# x-IMU3-SA-A8.net
KiCad netlist of a schematic drawn in Altium Designer
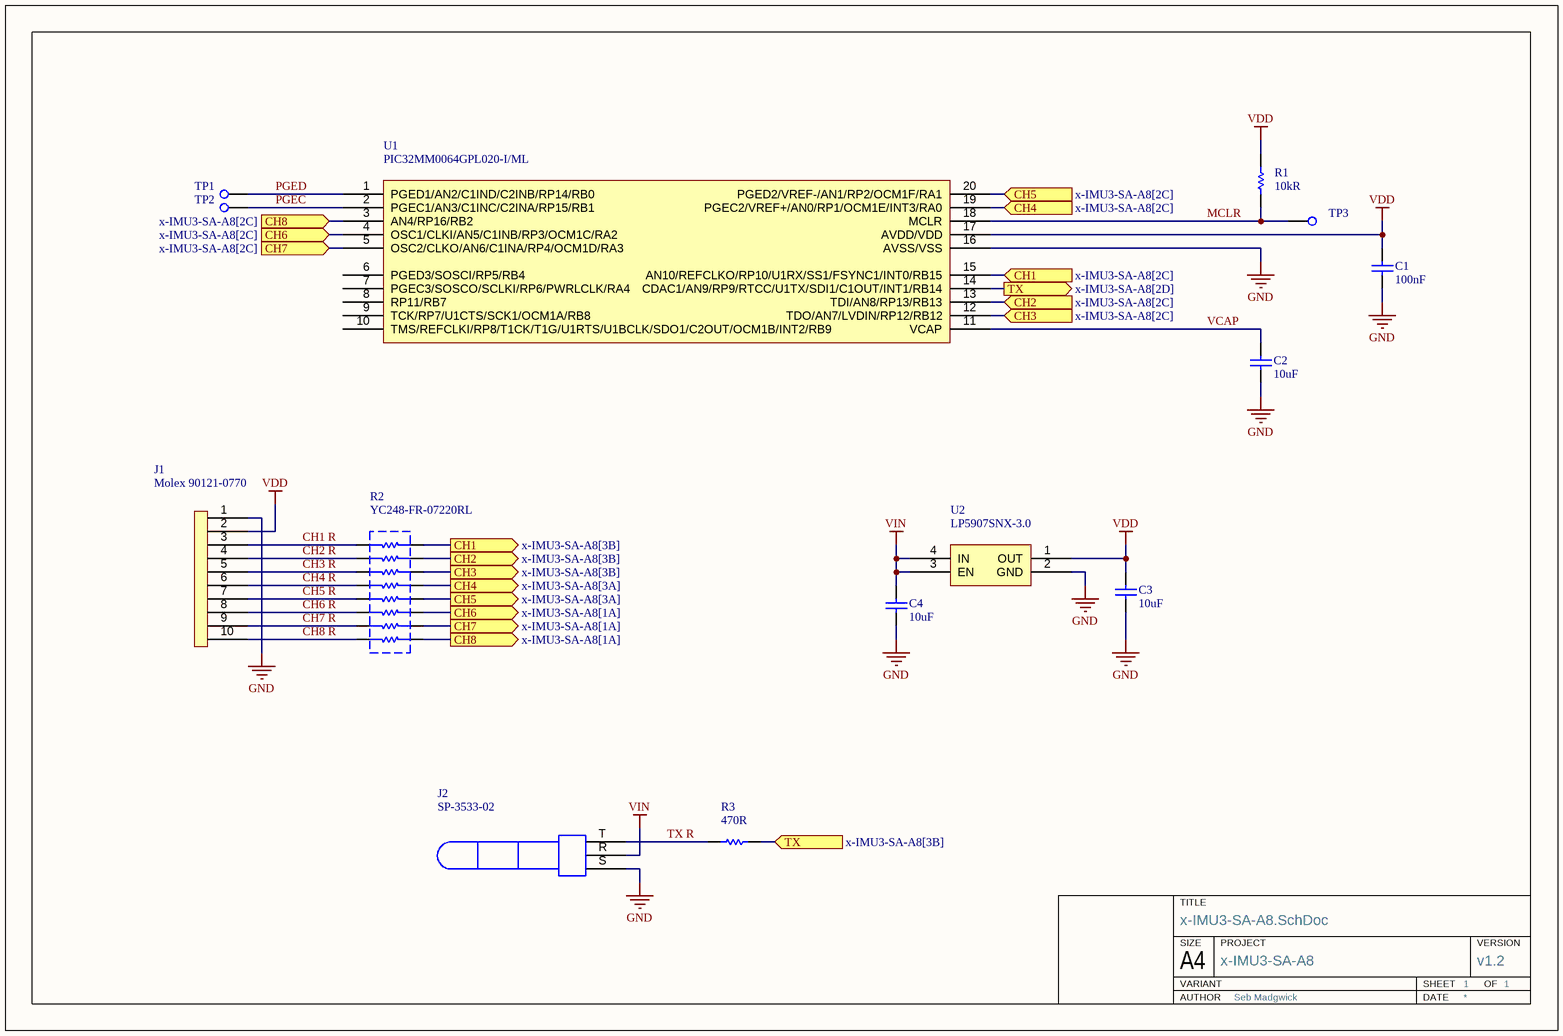
[diagram p0: x-IMU3-SA-A8.SchDoc]

(export (version "E")
  (design (tool "Eeschema 10.0.6"))
  (components
    (comp (ref "C1") (value "100nF") (footprint "Capacitor 0402") (libsource (lib "x-io") (part "Capacitor")))
    (comp (ref "C2") (value "10uF") (footprint "Capacitor 0402") (libsource (lib "x-io") (part "Capacitor")))
    (comp (ref "C3") (value "10uF") (footprint "Capacitor 0402") (libsource (lib "x-io") (part "Capacitor")))
    (comp (ref "C4") (value "10uF") (footprint "Capacitor 0402") (libsource (lib "x-io") (part "Capacitor")))
    (comp (ref "J1")
      (value "Molex 90121-0770")
      (footprint "Molex 90121-0770")
      (libsource (lib "x-io") (part "Molex 90121-0770"))
    )
    (comp (ref "J2")
      (value "SP-3533-02")
      (footprint "SP-3533-02")
      (libsource (lib "x-io") (part "SP-3533-02"))
    )
    (comp (ref "R1") (value "10kR") (footprint "Resistor 0402") (libsource (lib "x-io") (part "Resistor")))
    (comp (ref "R2")
      (value "YC248-FR-07220RL")
      (footprint "YC248")
      (libsource (lib "x-io") (part "Resistor Array 8"))
    )
    (comp (ref "R3") (value "470R") (footprint "Resistor 0402") (libsource (lib "x-io") (part "Resistor")))
    (comp (ref "TP1")
      (value "Test Point")
      (footprint "Test Point 1mm")
      (libsource (lib "x-io") (part "Test Point"))
    )
    (comp (ref "TP2")
      (value "Test Point")
      (footprint "Test Point 1mm")
      (libsource (lib "x-io") (part "Test Point"))
    )
    (comp (ref "TP3")
      (value "Test Point")
      (footprint "Test Point 1mm")
      (libsource (lib "x-io") (part "Test Point"))
    )
    (comp (ref "U1")
      (value "PIC32MM0064GPL020-I/ML")
      (footprint "QFN-20")
      (libsource (lib "x-io") (part "PIC32MM0064GPL020-I/ML"))
    )
    (comp (ref "U2")
      (value "LP5907SNX-3.0")
      (footprint "X2SON")
      (libsource (lib "x-io") (part "LP5907SNX-X.X"))
    )
  )
  (nets
    (net (code "1") (name "/CH1") (class "Default")
      (node (ref "R2") (pin "1") (pinfunction "1_1") (pintype "passive"))
      (node (ref "U1") (pin "15") (pinfunction "AN10/REFCLKO/RP10/U1RX/SS1/FSYNC1/INT0/RB15_15") (pintype "passive"))
    )
    (net (code "2") (name "/CH1 R") (class "Default")
      (node (ref "J1") (pin "3") (pinfunction "3_3") (pintype "passive"))
      (node (ref "R2") (pin "16") (pinfunction "16_16") (pintype "passive"))
    )
    (net (code "3") (name "/CH2") (class "Default")
      (node (ref "R2") (pin "2") (pinfunction "2_2") (pintype "passive"))
      (node (ref "U1") (pin "13") (pinfunction "TDI/AN8/RP13/RB13_13") (pintype "passive"))
    )
    (net (code "4") (name "/CH2 R") (class "Default")
      (node (ref "J1") (pin "4") (pinfunction "4_4") (pintype "passive"))
      (node (ref "R2") (pin "15") (pinfunction "15_15") (pintype "passive"))
    )
    (net (code "5") (name "/CH3") (class "Default")
      (node (ref "R2") (pin "3") (pinfunction "3_3") (pintype "passive"))
      (node (ref "U1") (pin "12") (pinfunction "TDO/AN7/LVDIN/RP12/RB12_12") (pintype "passive"))
    )
    (net (code "6") (name "/CH3 R") (class "Default")
      (node (ref "J1") (pin "5") (pinfunction "5_5") (pintype "passive"))
      (node (ref "R2") (pin "14") (pinfunction "14_14") (pintype "passive"))
    )
    (net (code "7") (name "/CH4") (class "Default")
      (node (ref "R2") (pin "4") (pinfunction "4_4") (pintype "passive"))
      (node (ref "U1") (pin "19") (pinfunction "PGEC2/VREF+/AN0/RP1/OCM1E/INT3/RA0_19") (pintype "passive"))
    )
    (net (code "8") (name "/CH4 R") (class "Default")
      (node (ref "J1") (pin "6") (pinfunction "6_6") (pintype "passive"))
      (node (ref "R2") (pin "13") (pinfunction "13_13") (pintype "passive"))
    )
    (net (code "9") (name "/CH5") (class "Default")
      (node (ref "R2") (pin "5") (pinfunction "5_5") (pintype "passive"))
      (node (ref "U1") (pin "20") (pinfunction "PGED2/VREF-/AN1/RP2/OCM1F/RA1_20") (pintype "passive"))
    )
    (net (code "10") (name "/CH5 R") (class "Default")
      (node (ref "J1") (pin "7") (pinfunction "7_7") (pintype "passive"))
      (node (ref "R2") (pin "12") (pinfunction "12_12") (pintype "passive"))
    )
    (net (code "11") (name "/CH6") (class "Default")
      (node (ref "R2") (pin "6") (pinfunction "6_6") (pintype "passive"))
      (node (ref "U1") (pin "4") (pinfunction "OSC1/CLKI/AN5/C1INB/RP3/OCM1C/RA2_4") (pintype "passive"))
    )
    (net (code "12") (name "/CH6 R") (class "Default")
      (node (ref "J1") (pin "8") (pinfunction "8_8") (pintype "passive"))
      (node (ref "R2") (pin "11") (pinfunction "11_11") (pintype "passive"))
    )
    (net (code "13") (name "/CH7") (class "Default")
      (node (ref "R2") (pin "7") (pinfunction "7_7") (pintype "passive"))
      (node (ref "U1") (pin "5") (pinfunction "OSC2/CLKO/AN6/C1INA/RP4/OCM1D/RA3_5") (pintype "passive"))
    )
    (net (code "14") (name "/CH7 R") (class "Default")
      (node (ref "J1") (pin "9") (pinfunction "9_9") (pintype "passive"))
      (node (ref "R2") (pin "10") (pinfunction "10_10") (pintype "passive"))
    )
    (net (code "15") (name "/CH8") (class "Default")
      (node (ref "R2") (pin "8") (pinfunction "8_8") (pintype "passive"))
      (node (ref "U1") (pin "3") (pinfunction "AN4/RP16/RB2_3") (pintype "passive"))
    )
    (net (code "16") (name "/CH8 R") (class "Default")
      (node (ref "J1") (pin "10") (pinfunction "10_10") (pintype "passive"))
      (node (ref "R2") (pin "9") (pinfunction "9_9") (pintype "passive"))
    )
    (net (code "17") (name "/MCLR") (class "Default")
      (node (ref "R1") (pin "1") (pinfunction "1_1") (pintype "passive"))
      (node (ref "TP3") (pin "1") (pinfunction "1_1") (pintype "passive"))
      (node (ref "U1") (pin "18") (pinfunction "MCLR_18") (pintype "passive"))
    )
    (net (code "18") (name "/PGEC") (class "Default")
      (node (ref "TP2") (pin "1") (pinfunction "1_1") (pintype "passive"))
      (node (ref "U1") (pin "2") (pinfunction "PGEC1/AN3/C1INC/C2INA/RP15/RB1_2") (pintype "passive"))
    )
    (net (code "19") (name "/PGED") (class "Default")
      (node (ref "TP1") (pin "1") (pinfunction "1_1") (pintype "passive"))
      (node (ref "U1") (pin "1") (pinfunction "PGED1/AN2/C1IND/C2INB/RP14/RB0_1") (pintype "passive"))
    )
    (net (code "20") (name "/TX") (class "Default")
      (node (ref "R3") (pin "2") (pinfunction "2_2") (pintype "passive"))
      (node (ref "U1") (pin "14") (pinfunction "CDAC1/AN9/RP9/RTCC/U1TX/SDI1/C1OUT/INT1/RB14_14") (pintype "passive"))
    )
    (net (code "21") (name "/TX R") (class "Default")
      (node (ref "J2") (pin "T") (pinfunction "T_T") (pintype "passive"))
      (node (ref "R3") (pin "1") (pinfunction "1_1") (pintype "passive"))
    )
    (net (code "22") (name "/VCAP") (class "Default")
      (node (ref "C2") (pin "2") (pinfunction "2_2") (pintype "passive"))
      (node (ref "U1") (pin "11") (pinfunction "VCAP_11") (pintype "passive"))
    )
    (net (code "23") (name "GND") (class "Default")
      (node (ref "C1") (pin "1") (pinfunction "1_1") (pintype "passive"))
      (node (ref "C2") (pin "1") (pinfunction "1_1") (pintype "passive"))
      (node (ref "C3") (pin "1") (pinfunction "1_1") (pintype "passive"))
      (node (ref "C4") (pin "1") (pinfunction "1_1") (pintype "passive"))
      (node (ref "J1") (pin "1") (pinfunction "1_1") (pintype "passive"))
      (node (ref "J2") (pin "S") (pinfunction "S_S") (pintype "passive"))
      (node (ref "U1") (pin "16") (pinfunction "AVSS/VSS_16") (pintype "passive"))
      (node (ref "U2") (pin "2") (pinfunction "GND_2") (pintype "passive"))
    )
    (net (code "24") (name "VDD") (class "Default")
      (node (ref "C1") (pin "2") (pinfunction "2_2") (pintype "passive"))
      (node (ref "C3") (pin "2") (pinfunction "2_2") (pintype "passive"))
      (node (ref "J1") (pin "2") (pinfunction "2_2") (pintype "passive"))
      (node (ref "R1") (pin "2") (pinfunction "2_2") (pintype "passive"))
      (node (ref "U1") (pin "17") (pinfunction "AVDD/VDD_17") (pintype "passive"))
      (node (ref "U2") (pin "1") (pinfunction "OUT_1") (pintype "passive"))
    )
    (net (code "25") (name "VIN") (class "Default")
      (node (ref "C4") (pin "2") (pinfunction "2_2") (pintype "passive"))
      (node (ref "J2") (pin "R") (pinfunction "R_R") (pintype "passive"))
      (node (ref "U2") (pin "3") (pinfunction "EN_3") (pintype "passive"))
      (node (ref "U2") (pin "4") (pinfunction "IN_4") (pintype "passive"))
    )
    (net (code "26") (name "unconnected-(U1-PGEC3{slash}SOSCO{slash}SCLKI{slash}RP6{slash}PWRLCLK{slash}RA4-Pad7)") (class "Default")
      (node (ref "U1") (pin "7") (pinfunction "PGEC3/SOSCO/SCLKI/RP6/PWRLCLK/RA4_7") (pintype "passive"))
    )
    (net (code "27") (name "unconnected-(U1-PGED3{slash}SOSCI{slash}RP5{slash}RB4-Pad6)") (class "Default")
      (node (ref "U1") (pin "6") (pinfunction "PGED3/SOSCI/RP5/RB4_6") (pintype "passive"))
    )
    (net (code "28") (name "unconnected-(U1-RP11{slash}RB7-Pad8)") (class "Default")
      (node (ref "U1") (pin "8") (pinfunction "RP11/RB7_8") (pintype "passive"))
    )
    (net (code "29") (name "unconnected-(U1-TCK{slash}RP7{slash}U1CTS{slash}SCK1{slash}OCM1A{slash}RB8-Pad9)") (class "Default")
      (node (ref "U1") (pin "9") (pinfunction "TCK/RP7/U1CTS/SCK1/OCM1A/RB8_9") (pintype "passive"))
    )
    (net (code "30") (name "unconnected-(U1-TMS{slash}REFCLKI{slash}RP8{slash}T1CK{slash}T1G{slash}U1RTS{slash}U1BCLK{slash}SDO1{slash}C2OUT{slash}OCM1B{slash}INT2{slash}RB9-Pad10)") (class "Default")
      (node (ref "U1") (pin "10") (pinfunction "TMS/REFCLKI/RP8/T1CK/T1G/U1RTS/U1BCLK/SDO1/C2OUT/OCM1B/INT2/RB9_10") (pintype "passive"))
    )
  )
)
